# schematic.net
KiCad netlist of a schematic drawn in Altium Designer
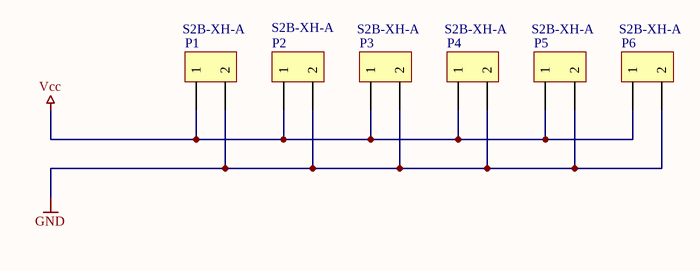
[diagram p0: schematic.SchDoc]

(export (version "E")
  (design (tool "Eeschema 10.0.6"))
  (components
    (comp (ref "P1")
      (value "S2B-XH-A")
      (footprint "S2B-XH-A")
      (description "JST pin header, 2.54 mm pitch, angled")
      (libsource (lib "symbols") (part "S2B-XH-A"))
    )
    (comp (ref "P2")
      (value "S2B-XH-A")
      (footprint "S2B-XH-A")
      (description "JST pin header, 2.54 mm pitch, angled")
      (libsource (lib "symbols") (part "S2B-XH-A"))
    )
    (comp (ref "P3")
      (value "S2B-XH-A")
      (footprint "S2B-XH-A")
      (description "JST pin header, 2.54 mm pitch, angled")
      (libsource (lib "symbols") (part "S2B-XH-A"))
    )
    (comp (ref "P4")
      (value "S2B-XH-A")
      (footprint "S2B-XH-A")
      (description "JST pin header, 2.54 mm pitch, angled")
      (libsource (lib "symbols") (part "S2B-XH-A"))
    )
    (comp (ref "P5")
      (value "S2B-XH-A")
      (footprint "S2B-XH-A")
      (description "JST pin header, 2.54 mm pitch, angled")
      (libsource (lib "symbols") (part "S2B-XH-A"))
    )
    (comp (ref "P6")
      (value "S2B-XH-A")
      (footprint "S2B-XH-A")
      (description "JST pin header, 2.54 mm pitch, angled")
      (libsource (lib "symbols") (part "S2B-XH-A"))
    )
  )
  (nets
    (net (code "1") (name "GND") (class "Default")
      (node (ref "P1") (pin "2") (pinfunction "2_2") (pintype "passive"))
      (node (ref "P2") (pin "2") (pinfunction "2_2") (pintype "passive"))
      (node (ref "P3") (pin "2") (pinfunction "2_2") (pintype "passive"))
      (node (ref "P4") (pin "2") (pinfunction "2_2") (pintype "passive"))
      (node (ref "P5") (pin "2") (pinfunction "2_2") (pintype "passive"))
      (node (ref "P6") (pin "2") (pinfunction "2_2") (pintype "passive"))
    )
    (net (code "2") (name "Vcc") (class "Default")
      (node (ref "P1") (pin "1") (pinfunction "1_1") (pintype "passive"))
      (node (ref "P2") (pin "1") (pinfunction "1_1") (pintype "passive"))
      (node (ref "P3") (pin "1") (pinfunction "1_1") (pintype "passive"))
      (node (ref "P4") (pin "1") (pinfunction "1_1") (pintype "passive"))
      (node (ref "P5") (pin "1") (pinfunction "1_1") (pintype "passive"))
      (node (ref "P6") (pin "1") (pinfunction "1_1") (pintype "passive"))
    )
  )
)
